# SparkFun_Level_Translator_PCA9306.net
KiCad netlist of a schematic drawn in EAGLE
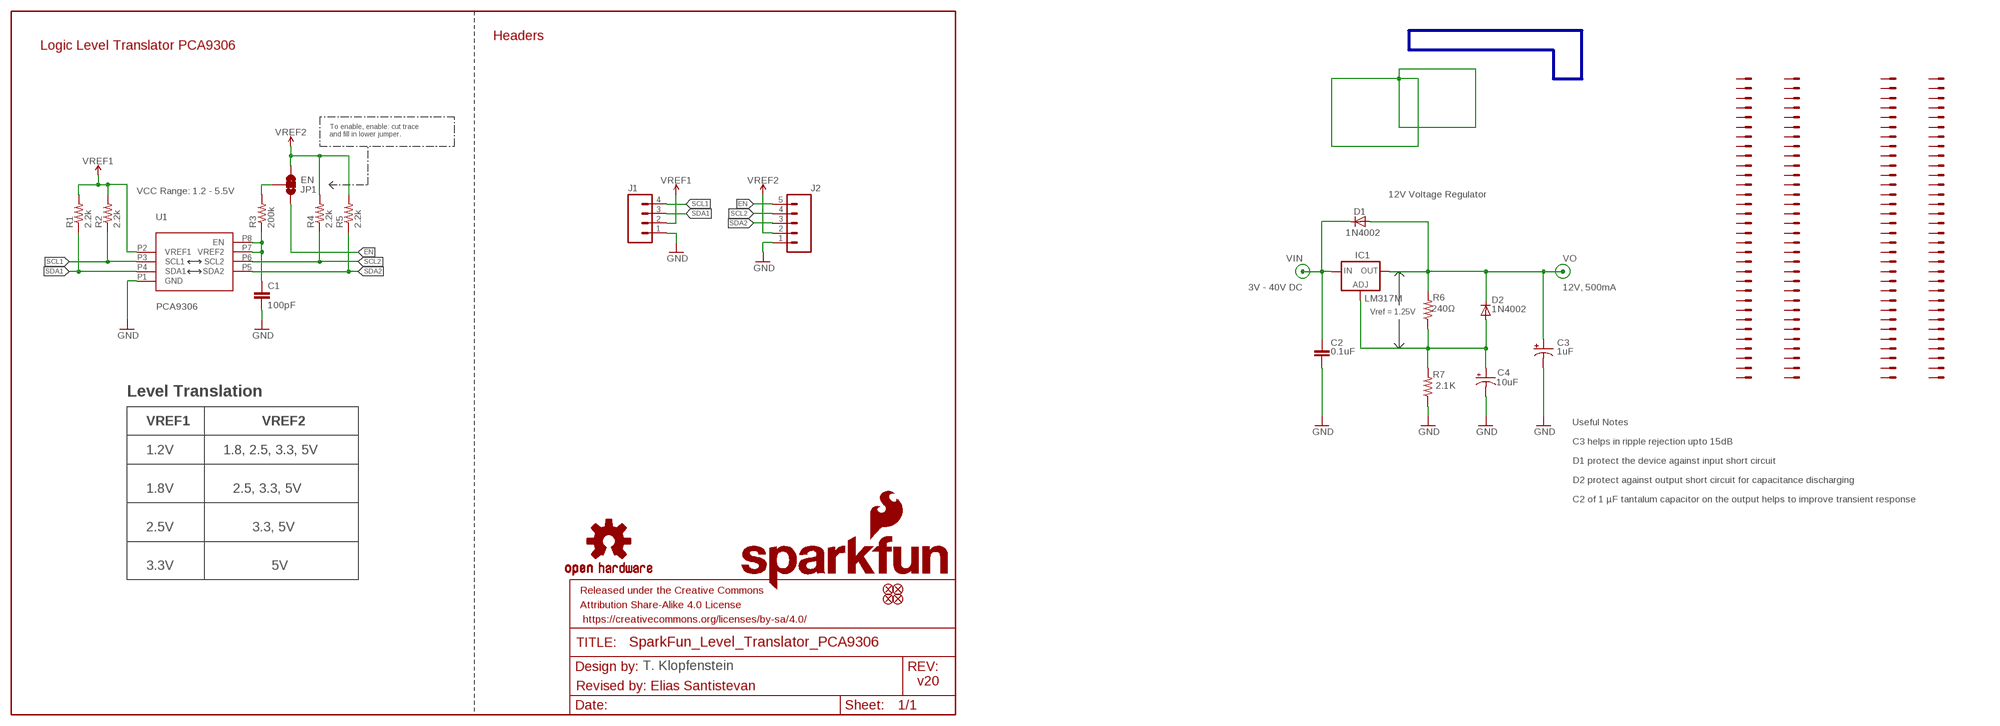
[diagram p0: schematic, sheet 1]

(export (version "E")
  (design (tool "Eeschema 10.0.6"))
  (components
    (comp (ref "C1")
      (value "100pF")
      (footprint "eagle-import:0603")
      (libsource (lib "eagle-import") (part "100PF-0603-50V-5%"))
    )
    (comp (ref "C2")
      (value "0.1uF")
      (footprint "eagle-import:C075-052X106")
      (libsource (lib "eagle-import") (part "C-EU075-052X106"))
    )
    (comp (ref "C3")
      (value "1uF")
      (footprint "eagle-import:085CS_1AR")
      (libsource (lib "eagle-import") (part "CPOL-US085CS-1AR"))
    )
    (comp (ref "C4")
      (value "10uF")
      (footprint "eagle-import:085CS_1AR")
      (libsource (lib "eagle-import") (part "CPOL-US085CS-1AR"))
    )
    (comp (ref "D1")
      (value "1N4002")
      (footprint "eagle-import:DO41-10")
      (libsource (lib "eagle-import") (part "1N4004"))
    )
    (comp (ref "D2")
      (value "1N4002")
      (footprint "eagle-import:DO41-10")
      (libsource (lib "eagle-import") (part "1N4004"))
    )
    (comp (ref "FD1")
      (value "FIDUCIALUFIDUCIAL")
      (footprint "eagle-import:FIDUCIAL-MICRO")
      (libsource (lib "eagle-import") (part "FIDUCIALUFIDUCIAL"))
    )
    (comp (ref "FD2")
      (value "FIDUCIALUFIDUCIAL")
      (footprint "eagle-import:FIDUCIAL-MICRO")
      (libsource (lib "eagle-import") (part "FIDUCIALUFIDUCIAL"))
    )
    (comp (ref "FD3")
      (value "FIDUCIALUFIDUCIAL")
      (footprint "eagle-import:FIDUCIAL-MICRO")
      (libsource (lib "eagle-import") (part "FIDUCIALUFIDUCIAL"))
    )
    (comp (ref "FD4")
      (value "FIDUCIALUFIDUCIAL")
      (footprint "eagle-import:FIDUCIAL-MICRO")
      (libsource (lib "eagle-import") (part "FIDUCIALUFIDUCIAL"))
    )
    (comp (ref "FRAME1")
      (value "FRAME-LETTER")
      (footprint "eagle-import:CREATIVE_COMMONS")
      (libsource (lib "eagle-import") (part "FRAME-LETTER"))
    )
    (comp (ref "IC1")
      (value "LM317MBSTT3")
      (footprint "eagle-import:SOT223")
      (fields (field (name "PARTNUMBER") "LM317M"))
      (libsource (lib "eagle-import") (part "LM317?MBSTT3"))
    )
    (comp (ref "J1")
      (value "CONN_041X04_NO_SILK")
      (footprint "eagle-import:1X04_NO_SILK")
      (libsource (lib "eagle-import") (part "CONN_041X04_NO_SILK"))
    )
    (comp (ref "J2")
      (value "CONN_05NO_SILK")
      (footprint "eagle-import:1X05_NO_SILK")
      (libsource (lib "eagle-import") (part "CONN_05NO_SILK"))
    )
    (comp (ref "J3")
      (value "6HE-100-VG64AC")
      (footprint "eagle-import:6HE_100-VG64AC")
      (libsource (lib "eagle-import") (part "6HE-?-VG64AC100"))
    )
    (comp (ref "JP1")
      (value "EN")
      (footprint "eagle-import:SMT-JUMPER_3_1-NC_TRACE_SILK")
      (libsource (lib "eagle-import") (part "JUMPER-SMT_3_1-NC_TRACE_SILK"))
    )
    (comp (ref "LOGO1")
      (value "OSHW-LOGOMINI")
      (footprint "eagle-import:OSHW-LOGO-MINI")
      (libsource (lib "eagle-import") (part "OSHW-LOGOMINI"))
    )
    (comp (ref "LOGO2")
      (value "SFE_LOGO_NAME.1_INCH")
      (footprint "eagle-import:SFE_LOGO_NAME_.1")
      (libsource (lib "eagle-import") (part "SFE_LOGO_NAME.1_INCH"))
    )
    (comp (ref "LOGO3")
      (value "SFE_LOGO_FLAME.1_INCH")
      (footprint "eagle-import:SFE_LOGO_FLAME_.1")
      (libsource (lib "eagle-import") (part "SFE_LOGO_FLAME.1_INCH"))
    )
    (comp (ref "R1")
      (value "2.2k")
      (footprint "eagle-import:0603")
      (libsource (lib "eagle-import") (part "2.2KOHM-0603-1/10W-1%"))
    )
    (comp (ref "R2")
      (value "2.2k")
      (footprint "eagle-import:0603")
      (libsource (lib "eagle-import") (part "2.2KOHM-0603-1/10W-1%"))
    )
    (comp (ref "R3")
      (value "200k")
      (footprint "eagle-import:0603")
      (libsource (lib "eagle-import") (part "200KOHM-0603-1/10W-1%"))
    )
    (comp (ref "R4")
      (value "2.2k")
      (footprint "eagle-import:0603")
      (libsource (lib "eagle-import") (part "2.2KOHM-0603-1/10W-1%"))
    )
    (comp (ref "R5")
      (value "2.2k")
      (footprint "eagle-import:0603")
      (libsource (lib "eagle-import") (part "2.2KOHM-0603-1/10W-1%"))
    )
    (comp (ref "R6")
      (value "240Ω")
      (footprint "eagle-import:M0805")
      (libsource (lib "eagle-import") (part "R-US_M0805"))
    )
    (comp (ref "R7")
      (value "2.1K")
      (footprint "eagle-import:M0805")
      (libsource (lib "eagle-import") (part "R-US_M0805"))
    )
    (comp (ref "U1")
      (value "PCA9306")
      (footprint "eagle-import:VSSOP_8PIN")
      (libsource (lib "eagle-import") (part "PCA9306VSSOP_8PIN"))
    )
  )
  (nets
    (net (code "1") (name "/VIN") (class "Default")
      (node (ref "C2") (pin "1") (pinfunction "1_1") (pintype "passive"))
      (node (ref "D1") (pin "C") (pinfunction "C_C") (pintype "passive"))
      (node (ref "IC1") (pin "3") (pinfunction "IN_3") (pintype "input"))
    )
    (net (code "2") (name "/VO") (class "Default")
      (node (ref "C3") (pin "+") (pinfunction "+_+") (pintype "passive"))
      (node (ref "D1") (pin "A") (pinfunction "A_A") (pintype "passive"))
      (node (ref "D2") (pin "C") (pinfunction "C_C") (pintype "passive"))
      (node (ref "IC1") (pin "4") (pinfunction "OUT_4") (pintype "passive"))
      (node (ref "R6") (pin "2") (pinfunction "2_2") (pintype "passive"))
    )
    (net (code "3") (name "EN") (class "Default")
      (node (ref "J2") (pin "5") (pinfunction "5_5") (pintype "passive"))
      (node (ref "JP1") (pin "1") (pinfunction "1_1") (pintype "passive"))
    )
    (net (code "4") (name "GND") (class "Default")
      (node (ref "C1") (pin "2") (pinfunction "2_2") (pintype "passive"))
      (node (ref "C2") (pin "2") (pinfunction "2_2") (pintype "passive"))
      (node (ref "C3") (pin "-") (pinfunction "-_-") (pintype "passive"))
      (node (ref "C4") (pin "-") (pinfunction "-_-") (pintype "passive"))
      (node (ref "J1") (pin "1") (pinfunction "1_1") (pintype "passive"))
      (node (ref "J2") (pin "1") (pinfunction "1_1") (pintype "passive"))
      (node (ref "R7") (pin "1") (pinfunction "1_1") (pintype "passive"))
      (node (ref "U1") (pin "P1") (pinfunction "GND_P1") (pintype "power_in"))
    )
    (net (code "5") (name "Net-(IC1-ADJ)") (class "Default")
      (node (ref "C4") (pin "+") (pinfunction "+_+") (pintype "passive"))
      (node (ref "D2") (pin "A") (pinfunction "A_A") (pintype "passive"))
      (node (ref "IC1") (pin "1") (pinfunction "ADJ_1") (pintype "input"))
      (node (ref "R6") (pin "1") (pinfunction "1_1") (pintype "passive"))
      (node (ref "R7") (pin "2") (pinfunction "2_2") (pintype "passive"))
    )
    (net (code "6") (name "Net-(JP1-Pad2)") (class "Default")
      (node (ref "JP1") (pin "2") (pinfunction "2_2") (pintype "passive"))
      (node (ref "R3") (pin "2") (pinfunction "2_2") (pintype "passive"))
    )
    (net (code "7") (name "Net-(U1-EN)") (class "Default")
      (node (ref "C1") (pin "1") (pinfunction "1_1") (pintype "passive"))
      (node (ref "R3") (pin "1") (pinfunction "1_1") (pintype "passive"))
      (node (ref "U1") (pin "P7") (pinfunction "VREF2_P7") (pintype "power_in"))
      (node (ref "U1") (pin "P8") (pinfunction "EN_P8") (pintype "input"))
    )
    (net (code "8") (name "SCL1") (class "Default")
      (node (ref "J1") (pin "4") (pinfunction "4_4") (pintype "passive"))
      (node (ref "R2") (pin "1") (pinfunction "1_1") (pintype "passive"))
      (node (ref "U1") (pin "P3") (pinfunction "SCL1_P3") (pintype "bidirectional"))
    )
    (net (code "9") (name "SCL2") (class "Default")
      (node (ref "J2") (pin "4") (pinfunction "4_4") (pintype "passive"))
      (node (ref "R4") (pin "1") (pinfunction "1_1") (pintype "passive"))
      (node (ref "U1") (pin "P6") (pinfunction "SCL2_P6") (pintype "bidirectional"))
    )
    (net (code "10") (name "SDA1") (class "Default")
      (node (ref "J1") (pin "3") (pinfunction "3_3") (pintype "passive"))
      (node (ref "R1") (pin "1") (pinfunction "1_1") (pintype "passive"))
      (node (ref "U1") (pin "P4") (pinfunction "SDA1_P4") (pintype "bidirectional"))
    )
    (net (code "11") (name "SDA2") (class "Default")
      (node (ref "J2") (pin "3") (pinfunction "3_3") (pintype "passive"))
      (node (ref "R5") (pin "1") (pinfunction "1_1") (pintype "passive"))
      (node (ref "U1") (pin "P5") (pinfunction "SDA2_P5") (pintype "bidirectional"))
    )
    (net (code "12") (name "VREF1") (class "Default")
      (node (ref "J1") (pin "2") (pinfunction "2_2") (pintype "passive"))
      (node (ref "R1") (pin "2") (pinfunction "2_2") (pintype "passive"))
      (node (ref "R2") (pin "2") (pinfunction "2_2") (pintype "passive"))
      (node (ref "U1") (pin "P2") (pinfunction "VREF1_P2") (pintype "power_in"))
    )
    (net (code "13") (name "VREF2") (class "Default")
      (node (ref "J2") (pin "2") (pinfunction "2_2") (pintype "passive"))
      (node (ref "JP1") (pin "3") (pinfunction "3_3") (pintype "passive"))
      (node (ref "R4") (pin "2") (pinfunction "2_2") (pintype "passive"))
      (node (ref "R5") (pin "2") (pinfunction "2_2") (pintype "passive"))
    )
    (net (code "14") (name "unconnected-(J3A-MSV-Pad1-A1)") (class "Default")
      (node (ref "J3") (pin "1-A1") (pinfunction "MSV_1-A1") (pintype "passive"))
    )
    (net (code "15") (name "unconnected-(J3AA-MS-Pad1-A4)") (class "Default")
      (node (ref "J3") (pin "1-A4") (pinfunction "MS_1-A4") (pintype "passive"))
    )
    (net (code "16") (name "unconnected-(J3AB-MS-Pad1-A5)") (class "Default")
      (node (ref "J3") (pin "1-A5") (pinfunction "MS_1-A5") (pintype "passive"))
    )
    (net (code "17") (name "unconnected-(J3AC-MS-Pad1-A6)") (class "Default")
      (node (ref "J3") (pin "1-A6") (pinfunction "MS_1-A6") (pintype "passive"))
    )
    (net (code "18") (name "unconnected-(J3AD-MS-Pad1-A7)") (class "Default")
      (node (ref "J3") (pin "1-A7") (pinfunction "MS_1-A7") (pintype "passive"))
    )
    (net (code "19") (name "unconnected-(J3AE-MS-Pad1-A8)") (class "Default")
      (node (ref "J3") (pin "1-A8") (pinfunction "MS_1-A8") (pintype "passive"))
    )
    (net (code "20") (name "unconnected-(J3AF-MS-Pad1-A9)") (class "Default")
      (node (ref "J3") (pin "1-A9") (pinfunction "MS_1-A9") (pintype "passive"))
    )
    (net (code "21") (name "unconnected-(J3AG-MSV-Pad1-C1)") (class "Default")
      (node (ref "J3") (pin "1-C1") (pinfunction "MSV_1-C1") (pintype "passive"))
    )
    (net (code "22") (name "unconnected-(J3AH-MS-Pad1-C10)") (class "Default")
      (node (ref "J3") (pin "1-C10") (pinfunction "MS_1-C10") (pintype "passive"))
    )
    (net (code "23") (name "unconnected-(J3AI-MS-Pad1-C11)") (class "Default")
      (node (ref "J3") (pin "1-C11") (pinfunction "MS_1-C11") (pintype "passive"))
    )
    (net (code "24") (name "unconnected-(J3AJ-MS-Pad1-C12)") (class "Default")
      (node (ref "J3") (pin "1-C12") (pinfunction "MS_1-C12") (pintype "passive"))
    )
    (net (code "25") (name "unconnected-(J3AK-MS-Pad1-C13)") (class "Default")
      (node (ref "J3") (pin "1-C13") (pinfunction "MS_1-C13") (pintype "passive"))
    )
    (net (code "26") (name "unconnected-(J3AL-MS-Pad1-C14)") (class "Default")
      (node (ref "J3") (pin "1-C14") (pinfunction "MS_1-C14") (pintype "passive"))
    )
    (net (code "27") (name "unconnected-(J3AM-MS-Pad1-C15)") (class "Default")
      (node (ref "J3") (pin "1-C15") (pinfunction "MS_1-C15") (pintype "passive"))
    )
    (net (code "28") (name "unconnected-(J3AN-MS-Pad1-C16)") (class "Default")
      (node (ref "J3") (pin "1-C16") (pinfunction "MS_1-C16") (pintype "passive"))
    )
    (net (code "29") (name "unconnected-(J3AO-MS-Pad1-C17)") (class "Default")
      (node (ref "J3") (pin "1-C17") (pinfunction "MS_1-C17") (pintype "passive"))
    )
    (net (code "30") (name "unconnected-(J3AP-MS-Pad1-C18)") (class "Default")
      (node (ref "J3") (pin "1-C18") (pinfunction "MS_1-C18") (pintype "passive"))
    )
    (net (code "31") (name "unconnected-(J3AQ-MS-Pad1-C19)") (class "Default")
      (node (ref "J3") (pin "1-C19") (pinfunction "MS_1-C19") (pintype "passive"))
    )
    (net (code "32") (name "unconnected-(J3AR-MS-Pad1-C2)") (class "Default")
      (node (ref "J3") (pin "1-C2") (pinfunction "MS_1-C2") (pintype "passive"))
    )
    (net (code "33") (name "unconnected-(J3AS-MS-Pad1-C20)") (class "Default")
      (node (ref "J3") (pin "1-C20") (pinfunction "MS_1-C20") (pintype "passive"))
    )
    (net (code "34") (name "unconnected-(J3AT-MS-Pad1-C21)") (class "Default")
      (node (ref "J3") (pin "1-C21") (pinfunction "MS_1-C21") (pintype "passive"))
    )
    (net (code "35") (name "unconnected-(J3AU-MS-Pad1-C22)") (class "Default")
      (node (ref "J3") (pin "1-C22") (pinfunction "MS_1-C22") (pintype "passive"))
    )
    (net (code "36") (name "unconnected-(J3AV-MS-Pad1-C23)") (class "Default")
      (node (ref "J3") (pin "1-C23") (pinfunction "MS_1-C23") (pintype "passive"))
    )
    (net (code "37") (name "unconnected-(J3AW-MS-Pad1-C24)") (class "Default")
      (node (ref "J3") (pin "1-C24") (pinfunction "MS_1-C24") (pintype "passive"))
    )
    (net (code "38") (name "unconnected-(J3AX-MS-Pad1-C25)") (class "Default")
      (node (ref "J3") (pin "1-C25") (pinfunction "MS_1-C25") (pintype "passive"))
    )
    (net (code "39") (name "unconnected-(J3AY-MS-Pad1-C26)") (class "Default")
      (node (ref "J3") (pin "1-C26") (pinfunction "MS_1-C26") (pintype "passive"))
    )
    (net (code "40") (name "unconnected-(J3AZ-MS-Pad1-C27)") (class "Default")
      (node (ref "J3") (pin "1-C27") (pinfunction "MS_1-C27") (pintype "passive"))
    )
    (net (code "41") (name "unconnected-(J3B-MS-Pad1-A10)") (class "Default")
      (node (ref "J3") (pin "1-A10") (pinfunction "MS_1-A10") (pintype "passive"))
    )
    (net (code "42") (name "unconnected-(J3BA-MS-Pad1-C28)") (class "Default")
      (node (ref "J3") (pin "1-C28") (pinfunction "MS_1-C28") (pintype "passive"))
    )
    (net (code "43") (name "unconnected-(J3BB-MS-Pad1-C29)") (class "Default")
      (node (ref "J3") (pin "1-C29") (pinfunction "MS_1-C29") (pintype "passive"))
    )
    (net (code "44") (name "unconnected-(J3BC-MS-Pad1-C3)") (class "Default")
      (node (ref "J3") (pin "1-C3") (pinfunction "MS_1-C3") (pintype "passive"))
    )
    (net (code "45") (name "unconnected-(J3BD-MS-Pad1-C30)") (class "Default")
      (node (ref "J3") (pin "1-C30") (pinfunction "MS_1-C30") (pintype "passive"))
    )
    (net (code "46") (name "unconnected-(J3BE-MS-Pad1-C31)") (class "Default")
      (node (ref "J3") (pin "1-C31") (pinfunction "MS_1-C31") (pintype "passive"))
    )
    (net (code "47") (name "unconnected-(J3BF-MS-Pad1-C32)") (class "Default")
      (node (ref "J3") (pin "1-C32") (pinfunction "MS_1-C32") (pintype "passive"))
    )
    (net (code "48") (name "unconnected-(J3BG-MS-Pad1-C4)") (class "Default")
      (node (ref "J3") (pin "1-C4") (pinfunction "MS_1-C4") (pintype "passive"))
    )
    (net (code "49") (name "unconnected-(J3BH-MS-Pad1-C5)") (class "Default")
      (node (ref "J3") (pin "1-C5") (pinfunction "MS_1-C5") (pintype "passive"))
    )
    (net (code "50") (name "unconnected-(J3BI-MS-Pad1-C6)") (class "Default")
      (node (ref "J3") (pin "1-C6") (pinfunction "MS_1-C6") (pintype "passive"))
    )
    (net (code "51") (name "unconnected-(J3BJ-MS-Pad1-C7)") (class "Default")
      (node (ref "J3") (pin "1-C7") (pinfunction "MS_1-C7") (pintype "passive"))
    )
    (net (code "52") (name "unconnected-(J3BK-MS-Pad1-C8)") (class "Default")
      (node (ref "J3") (pin "1-C8") (pinfunction "MS_1-C8") (pintype "passive"))
    )
    (net (code "53") (name "unconnected-(J3BL-MS-Pad1-C9)") (class "Default")
      (node (ref "J3") (pin "1-C9") (pinfunction "MS_1-C9") (pintype "passive"))
    )
    (net (code "54") (name "unconnected-(J3BM-MSV-Pad2-A1)") (class "Default")
      (node (ref "J3") (pin "2-A1") (pinfunction "MSV_2-A1") (pintype "passive"))
    )
    (net (code "55") (name "unconnected-(J3BN-MS-Pad2-A10)") (class "Default")
      (node (ref "J3") (pin "2-A10") (pinfunction "MS_2-A10") (pintype "passive"))
    )
    (net (code "56") (name "unconnected-(J3BO-MS-Pad2-A11)") (class "Default")
      (node (ref "J3") (pin "2-A11") (pinfunction "MS_2-A11") (pintype "passive"))
    )
    (net (code "57") (name "unconnected-(J3BP-MS-Pad2-A12)") (class "Default")
      (node (ref "J3") (pin "2-A12") (pinfunction "MS_2-A12") (pintype "passive"))
    )
    (net (code "58") (name "unconnected-(J3BQ-MS-Pad2-A13)") (class "Default")
      (node (ref "J3") (pin "2-A13") (pinfunction "MS_2-A13") (pintype "passive"))
    )
    (net (code "59") (name "unconnected-(J3BR-MS-Pad2-A14)") (class "Default")
      (node (ref "J3") (pin "2-A14") (pinfunction "MS_2-A14") (pintype "passive"))
    )
    (net (code "60") (name "unconnected-(J3BS-MS-Pad2-A15)") (class "Default")
      (node (ref "J3") (pin "2-A15") (pinfunction "MS_2-A15") (pintype "passive"))
    )
    (net (code "61") (name "unconnected-(J3BT-MS-Pad2-A16)") (class "Default")
      (node (ref "J3") (pin "2-A16") (pinfunction "MS_2-A16") (pintype "passive"))
    )
    (net (code "62") (name "unconnected-(J3BU-MS-Pad2-A17)") (class "Default")
      (node (ref "J3") (pin "2-A17") (pinfunction "MS_2-A17") (pintype "passive"))
    )
    (net (code "63") (name "unconnected-(J3BV-MS-Pad2-A18)") (class "Default")
      (node (ref "J3") (pin "2-A18") (pinfunction "MS_2-A18") (pintype "passive"))
    )
    (net (code "64") (name "unconnected-(J3BW-MS-Pad2-A19)") (class "Default")
      (node (ref "J3") (pin "2-A19") (pinfunction "MS_2-A19") (pintype "passive"))
    )
    (net (code "65") (name "unconnected-(J3BX-MS-Pad2-A2)") (class "Default")
      (node (ref "J3") (pin "2-A2") (pinfunction "MS_2-A2") (pintype "passive"))
    )
    (net (code "66") (name "unconnected-(J3BY-MS-Pad2-A20)") (class "Default")
      (node (ref "J3") (pin "2-A20") (pinfunction "MS_2-A20") (pintype "passive"))
    )
    (net (code "67") (name "unconnected-(J3BZ-MS-Pad2-A21)") (class "Default")
      (node (ref "J3") (pin "2-A21") (pinfunction "MS_2-A21") (pintype "passive"))
    )
    (net (code "68") (name "unconnected-(J3C-MS-Pad1-A11)") (class "Default")
      (node (ref "J3") (pin "1-A11") (pinfunction "MS_1-A11") (pintype "passive"))
    )
    (net (code "69") (name "unconnected-(J3CA-MS-Pad2-A22)") (class "Default")
      (node (ref "J3") (pin "2-A22") (pinfunction "MS_2-A22") (pintype "passive"))
    )
    (net (code "70") (name "unconnected-(J3CB-MS-Pad2-A23)") (class "Default")
      (node (ref "J3") (pin "2-A23") (pinfunction "MS_2-A23") (pintype "passive"))
    )
    (net (code "71") (name "unconnected-(J3CC-MS-Pad2-A24)") (class "Default")
      (node (ref "J3") (pin "2-A24") (pinfunction "MS_2-A24") (pintype "passive"))
    )
    (net (code "72") (name "unconnected-(J3CD-MS-Pad2-A25)") (class "Default")
      (node (ref "J3") (pin "2-A25") (pinfunction "MS_2-A25") (pintype "passive"))
    )
    (net (code "73") (name "unconnected-(J3CE-MS-Pad2-A26)") (class "Default")
      (node (ref "J3") (pin "2-A26") (pinfunction "MS_2-A26") (pintype "passive"))
    )
    (net (code "74") (name "unconnected-(J3CF-MS-Pad2-A27)") (class "Default")
      (node (ref "J3") (pin "2-A27") (pinfunction "MS_2-A27") (pintype "passive"))
    )
    (net (code "75") (name "unconnected-(J3CG-MS-Pad2-A28)") (class "Default")
      (node (ref "J3") (pin "2-A28") (pinfunction "MS_2-A28") (pintype "passive"))
    )
    (net (code "76") (name "unconnected-(J3CH-MS-Pad2-A29)") (class "Default")
      (node (ref "J3") (pin "2-A29") (pinfunction "MS_2-A29") (pintype "passive"))
    )
    (net (code "77") (name "unconnected-(J3CI-MS-Pad2-A3)") (class "Default")
      (node (ref "J3") (pin "2-A3") (pinfunction "MS_2-A3") (pintype "passive"))
    )
    (net (code "78") (name "unconnected-(J3CJ-MS-Pad2-A30)") (class "Default")
      (node (ref "J3") (pin "2-A30") (pinfunction "MS_2-A30") (pintype "passive"))
    )
    (net (code "79") (name "unconnected-(J3CK-MS-Pad2-A31)") (class "Default")
      (node (ref "J3") (pin "2-A31") (pinfunction "MS_2-A31") (pintype "passive"))
    )
    (net (code "80") (name "unconnected-(J3CL-MS-Pad2-A32)") (class "Default")
      (node (ref "J3") (pin "2-A32") (pinfunction "MS_2-A32") (pintype "passive"))
    )
    (net (code "81") (name "unconnected-(J3CM-MS-Pad2-A4)") (class "Default")
      (node (ref "J3") (pin "2-A4") (pinfunction "MS_2-A4") (pintype "passive"))
    )
    (net (code "82") (name "unconnected-(J3CN-MS-Pad2-A5)") (class "Default")
      (node (ref "J3") (pin "2-A5") (pinfunction "MS_2-A5") (pintype "passive"))
    )
    (net (code "83") (name "unconnected-(J3CO-MS-Pad2-A6)") (class "Default")
      (node (ref "J3") (pin "2-A6") (pinfunction "MS_2-A6") (pintype "passive"))
    )
    (net (code "84") (name "unconnected-(J3CP-MS-Pad2-A7)") (class "Default")
      (node (ref "J3") (pin "2-A7") (pinfunction "MS_2-A7") (pintype "passive"))
    )
    (net (code "85") (name "unconnected-(J3CQ-MS-Pad2-A8)") (class "Default")
      (node (ref "J3") (pin "2-A8") (pinfunction "MS_2-A8") (pintype "passive"))
    )
    (net (code "86") (name "unconnected-(J3CR-MS-Pad2-A9)") (class "Default")
      (node (ref "J3") (pin "2-A9") (pinfunction "MS_2-A9") (pintype "passive"))
    )
    (net (code "87") (name "unconnected-(J3CS-MSV-Pad2-C1)") (class "Default")
      (node (ref "J3") (pin "2-C1") (pinfunction "MSV_2-C1") (pintype "passive"))
    )
    (net (code "88") (name "unconnected-(J3CT-MS-Pad2-C10)") (class "Default")
      (node (ref "J3") (pin "2-C10") (pinfunction "MS_2-C10") (pintype "passive"))
    )
    (net (code "89") (name "unconnected-(J3CU-MS-Pad2-C11)") (class "Default")
      (node (ref "J3") (pin "2-C11") (pinfunction "MS_2-C11") (pintype "passive"))
    )
    (net (code "90") (name "unconnected-(J3CV-MS-Pad2-C12)") (class "Default")
      (node (ref "J3") (pin "2-C12") (pinfunction "MS_2-C12") (pintype "passive"))
    )
    (net (code "91") (name "unconnected-(J3CW-MS-Pad2-C13)") (class "Default")
      (node (ref "J3") (pin "2-C13") (pinfunction "MS_2-C13") (pintype "passive"))
    )
    (net (code "92") (name "unconnected-(J3CX-MS-Pad2-C14)") (class "Default")
      (node (ref "J3") (pin "2-C14") (pinfunction "MS_2-C14") (pintype "passive"))
    )
    (net (code "93") (name "unconnected-(J3CY-MS-Pad2-C15)") (class "Default")
      (node (ref "J3") (pin "2-C15") (pinfunction "MS_2-C15") (pintype "passive"))
    )
    (net (code "94") (name "unconnected-(J3CZ-MS-Pad2-C16)") (class "Default")
      (node (ref "J3") (pin "2-C16") (pinfunction "MS_2-C16") (pintype "passive"))
    )
    (net (code "95") (name "unconnected-(J3D-MS-Pad1-A12)") (class "Default")
      (node (ref "J3") (pin "1-A12") (pinfunction "MS_1-A12") (pintype "passive"))
    )
    (net (code "96") (name "unconnected-(J3DA-MS-Pad2-C17)") (class "Default")
      (node (ref "J3") (pin "2-C17") (pinfunction "MS_2-C17") (pintype "passive"))
    )
    (net (code "97") (name "unconnected-(J3DB-MS-Pad2-C18)") (class "Default")
      (node (ref "J3") (pin "2-C18") (pinfunction "MS_2-C18") (pintype "passive"))
    )
    (net (code "98") (name "unconnected-(J3DC-MS-Pad2-C19)") (class "Default")
      (node (ref "J3") (pin "2-C19") (pinfunction "MS_2-C19") (pintype "passive"))
    )
    (net (code "99") (name "unconnected-(J3DD-MS-Pad2-C2)") (class "Default")
      (node (ref "J3") (pin "2-C2") (pinfunction "MS_2-C2") (pintype "passive"))
    )
    (net (code "100") (name "unconnected-(J3DE-MS-Pad2-C20)") (class "Default")
      (node (ref "J3") (pin "2-C20") (pinfunction "MS_2-C20") (pintype "passive"))
    )
    (net (code "101") (name "unconnected-(J3DF-MS-Pad2-C21)") (class "Default")
      (node (ref "J3") (pin "2-C21") (pinfunction "MS_2-C21") (pintype "passive"))
    )
    (net (code "102") (name "unconnected-(J3DG-MS-Pad2-C22)") (class "Default")
      (node (ref "J3") (pin "2-C22") (pinfunction "MS_2-C22") (pintype "passive"))
    )
    (net (code "103") (name "unconnected-(J3DH-MS-Pad2-C23)") (class "Default")
      (node (ref "J3") (pin "2-C23") (pinfunction "MS_2-C23") (pintype "passive"))
    )
    (net (code "104") (name "unconnected-(J3DI-MS-Pad2-C24)") (class "Default")
      (node (ref "J3") (pin "2-C24") (pinfunction "MS_2-C24") (pintype "passive"))
    )
    (net (code "105") (name "unconnected-(J3DJ-MS-Pad2-C25)") (class "Default")
      (node (ref "J3") (pin "2-C25") (pinfunction "MS_2-C25") (pintype "passive"))
    )
    (net (code "106") (name "unconnected-(J3DK-MS-Pad2-C26)") (class "Default")
      (node (ref "J3") (pin "2-C26") (pinfunction "MS_2-C26") (pintype "passive"))
    )
    (net (code "107") (name "unconnected-(J3DL-MS-Pad2-C27)") (class "Default")
      (node (ref "J3") (pin "2-C27") (pinfunction "MS_2-C27") (pintype "passive"))
    )
    (net (code "108") (name "unconnected-(J3DM-MS-Pad2-C28)") (class "Default")
      (node (ref "J3") (pin "2-C28") (pinfunction "MS_2-C28") (pintype "passive"))
    )
    (net (code "109") (name "unconnected-(J3DN-MS-Pad2-C29)") (class "Default")
      (node (ref "J3") (pin "2-C29") (pinfunction "MS_2-C29") (pintype "passive"))
    )
    (net (code "110") (name "unconnected-(J3DO-MS-Pad2-C3)") (class "Default")
      (node (ref "J3") (pin "2-C3") (pinfunction "MS_2-C3") (pintype "passive"))
    )
    (net (code "111") (name "unconnected-(J3DP-MS-Pad2-C30)") (class "Default")
      (node (ref "J3") (pin "2-C30") (pinfunction "MS_2-C30") (pintype "passive"))
    )
    (net (code "112") (name "unconnected-(J3DQ-MS-Pad2-C31)") (class "Default")
      (node (ref "J3") (pin "2-C31") (pinfunction "MS_2-C31") (pintype "passive"))
    )
    (net (code "113") (name "unconnected-(J3DR-MS-Pad2-C32)") (class "Default")
      (node (ref "J3") (pin "2-C32") (pinfunction "MS_2-C32") (pintype "passive"))
    )
    (net (code "114") (name "unconnected-(J3DS-MS-Pad2-C4)") (class "Default")
      (node (ref "J3") (pin "2-C4") (pinfunction "MS_2-C4") (pintype "passive"))
    )
    (net (code "115") (name "unconnected-(J3DT-MS-Pad2-C5)") (class "Default")
      (node (ref "J3") (pin "2-C5") (pinfunction "MS_2-C5") (pintype "passive"))
    )
    (net (code "116") (name "unconnected-(J3DU-MS-Pad2-C6)") (class "Default")
      (node (ref "J3") (pin "2-C6") (pinfunction "MS_2-C6") (pintype "passive"))
    )
    (net (code "117") (name "unconnected-(J3DV-MS-Pad2-C7)") (class "Default")
      (node (ref "J3") (pin "2-C7") (pinfunction "MS_2-C7") (pintype "passive"))
    )
    (net (code "118") (name "unconnected-(J3DW-MS-Pad2-C8)") (class "Default")
      (node (ref "J3") (pin "2-C8") (pinfunction "MS_2-C8") (pintype "passive"))
    )
    (net (code "119") (name "unconnected-(J3DX-MS-Pad2-C9)") (class "Default")
      (node (ref "J3") (pin "2-C9") (pinfunction "MS_2-C9") (pintype "passive"))
    )
    (net (code "120") (name "unconnected-(J3E-MS-Pad1-A13)") (class "Default")
      (node (ref "J3") (pin "1-A13") (pinfunction "MS_1-A13") (pintype "passive"))
    )
    (net (code "121") (name "unconnected-(J3F-MS-Pad1-A14)") (class "Default")
      (node (ref "J3") (pin "1-A14") (pinfunction "MS_1-A14") (pintype "passive"))
    )
    (net (code "122") (name "unconnected-(J3G-MS-Pad1-A15)") (class "Default")
      (node (ref "J3") (pin "1-A15") (pinfunction "MS_1-A15") (pintype "passive"))
    )
    (net (code "123") (name "unconnected-(J3H-MS-Pad1-A16)") (class "Default")
      (node (ref "J3") (pin "1-A16") (pinfunction "MS_1-A16") (pintype "passive"))
    )
    (net (code "124") (name "unconnected-(J3I-MS-Pad1-A17)") (class "Default")
      (node (ref "J3") (pin "1-A17") (pinfunction "MS_1-A17") (pintype "passive"))
    )
    (net (code "125") (name "unconnected-(J3J-MS-Pad1-A18)") (class "Default")
      (node (ref "J3") (pin "1-A18") (pinfunction "MS_1-A18") (pintype "passive"))
    )
    (net (code "126") (name "unconnected-(J3K-MS-Pad1-A19)") (class "Default")
      (node (ref "J3") (pin "1-A19") (pinfunction "MS_1-A19") (pintype "passive"))
    )
    (net (code "127") (name "unconnected-(J3L-MS-Pad1-A2)") (class "Default")
      (node (ref "J3") (pin "1-A2") (pinfunction "MS_1-A2") (pintype "passive"))
    )
    (net (code "128") (name "unconnected-(J3M-MS-Pad1-A20)") (class "Default")
      (node (ref "J3") (pin "1-A20") (pinfunction "MS_1-A20") (pintype "passive"))
    )
    (net (code "129") (name "unconnected-(J3N-MS-Pad1-A21)") (class "Default")
      (node (ref "J3") (pin "1-A21") (pinfunction "MS_1-A21") (pintype "passive"))
    )
    (net (code "130") (name "unconnected-(J3O-MS-Pad1-A22)") (class "Default")
      (node (ref "J3") (pin "1-A22") (pinfunction "MS_1-A22") (pintype "passive"))
    )
    (net (code "131") (name "unconnected-(J3P-MS-Pad1-A23)") (class "Default")
      (node (ref "J3") (pin "1-A23") (pinfunction "MS_1-A23") (pintype "passive"))
    )
    (net (code "132") (name "unconnected-(J3Q-MS-Pad1-A24)") (class "Default")
      (node (ref "J3") (pin "1-A24") (pinfunction "MS_1-A24") (pintype "passive"))
    )
    (net (code "133") (name "unconnected-(J3R-MS-Pad1-A25)") (class "Default")
      (node (ref "J3") (pin "1-A25") (pinfunction "MS_1-A25") (pintype "passive"))
    )
    (net (code "134") (name "unconnected-(J3S-MS-Pad1-A26)") (class "Default")
      (node (ref "J3") (pin "1-A26") (pinfunction "MS_1-A26") (pintype "passive"))
    )
    (net (code "135") (name "unconnected-(J3T-MS-Pad1-A27)") (class "Default")
      (node (ref "J3") (pin "1-A27") (pinfunction "MS_1-A27") (pintype "passive"))
    )
    (net (code "136") (name "unconnected-(J3U-MS-Pad1-A28)") (class "Default")
      (node (ref "J3") (pin "1-A28") (pinfunction "MS_1-A28") (pintype "passive"))
    )
    (net (code "137") (name "unconnected-(J3V-MS-Pad1-A29)") (class "Default")
      (node (ref "J3") (pin "1-A29") (pinfunction "MS_1-A29") (pintype "passive"))
    )
    (net (code "138") (name "unconnected-(J3W-MS-Pad1-A3)") (class "Default")
      (node (ref "J3") (pin "1-A3") (pinfunction "MS_1-A3") (pintype "passive"))
    )
    (net (code "139") (name "unconnected-(J3X-MS-Pad1-A30)") (class "Default")
      (node (ref "J3") (pin "1-A30") (pinfunction "MS_1-A30") (pintype "passive"))
    )
    (net (code "140") (name "unconnected-(J3Y-MS-Pad1-A31)") (class "Default")
      (node (ref "J3") (pin "1-A31") (pinfunction "MS_1-A31") (pintype "passive"))
    )
    (net (code "141") (name "unconnected-(J3Z-MS-Pad1-A32)") (class "Default")
      (node (ref "J3") (pin "1-A32") (pinfunction "MS_1-A32") (pintype "passive"))
    )
  )
)
